# tes1.net
KiCad netlist of a schematic drawn in EAGLE
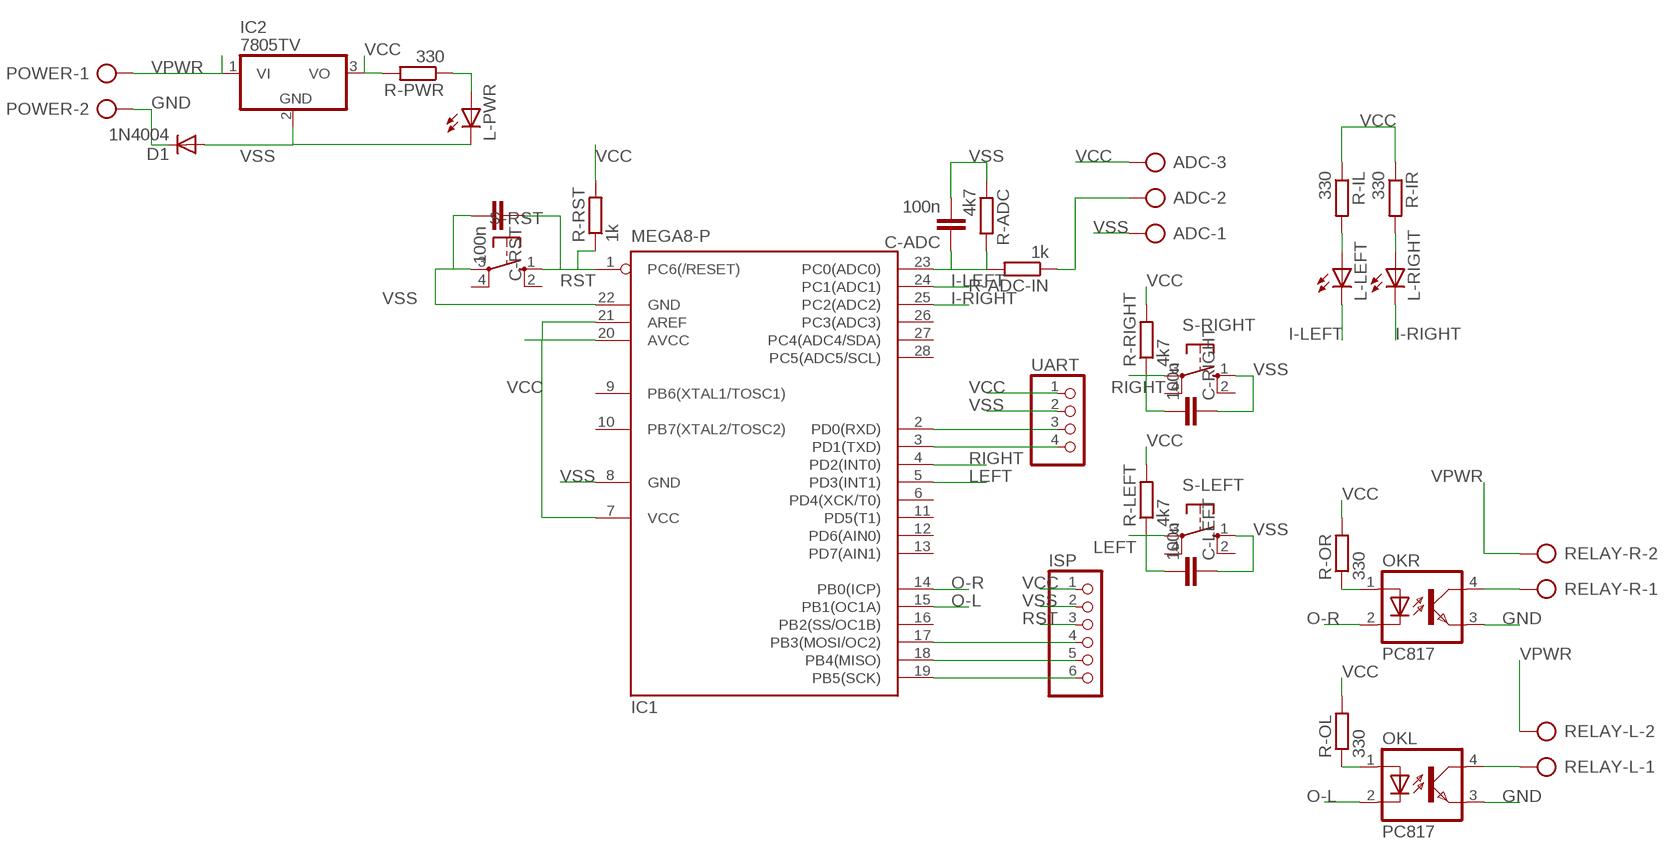
[diagram p0: schematic, sheet 1]

(export (version "E")
  (design (tool "Eeschema 10.0.6"))
  (components
    (comp (ref "ADC")
      (value "AK300/3")
      (footprint "eagle-import:AK300_3")
      (libsource (lib "eagle-import") (part "AK300/3"))
    )
    (comp (ref "C-ADC")
      (value "100n")
      (footprint "eagle-import:C050-024X044")
      (libsource (lib "eagle-import") (part "C-EU050-024X044"))
    )
    (comp (ref "C-LEFT")
      (value "100n")
      (footprint "eagle-import:C050-024X044")
      (libsource (lib "eagle-import") (part "C-EU050-024X044"))
    )
    (comp (ref "C-RIGHT")
      (value "100n")
      (footprint "eagle-import:C050-024X044")
      (libsource (lib "eagle-import") (part "C-EU050-024X044"))
    )
    (comp (ref "C-RST")
      (value "100n")
      (footprint "eagle-import:C050-024X044")
      (libsource (lib "eagle-import") (part "C-EU050-024X044"))
    )
    (comp (ref "D1")
      (value "1N4004")
      (footprint "eagle-import:DO41-10")
      (libsource (lib "eagle-import") (part "1N4004"))
    )
    (comp (ref "IC1")
      (value "MEGA8-P")
      (footprint "eagle-import:DIL28-3")
      (libsource (lib "eagle-import") (part "MEGA8-P"))
    )
    (comp (ref "IC2")
      (value "7805TV")
      (footprint "eagle-import:TO220V")
      (libsource (lib "eagle-import") (part "78TV05"))
    )
    (comp (ref "ISP")
      (value "PINHD-1X6")
      (footprint "eagle-import:1X06")
      (libsource (lib "eagle-import") (part "PINHD-1X6"))
    )
    (comp (ref "L-LEFT")
      (value "LED3MM")
      (footprint "eagle-import:LED3MM")
      (libsource (lib "eagle-import") (part "LED3MM"))
    )
    (comp (ref "L-PWR")
      (value "LED3MM")
      (footprint "eagle-import:LED3MM")
      (libsource (lib "eagle-import") (part "LED3MM"))
    )
    (comp (ref "L-RIGHT")
      (value "LED3MM")
      (footprint "eagle-import:LED3MM")
      (libsource (lib "eagle-import") (part "LED3MM"))
    )
    (comp (ref "OKL")
      (value "PC817")
      (footprint "eagle-import:DIL04")
      (fields (field (name "MPN") "PC817X4J000F"))
      (libsource (lib "eagle-import") (part "PC817"))
    )
    (comp (ref "OKR")
      (value "PC817")
      (footprint "eagle-import:DIL04")
      (fields (field (name "MPN") "PC817X4J000F"))
      (libsource (lib "eagle-import") (part "PC817"))
    )
    (comp (ref "POWER")
      (value "AK300/2")
      (footprint "eagle-import:AK300_2")
      (libsource (lib "eagle-import") (part "AK300/2"))
    )
    (comp (ref "R-ADC")
      (value "4k7")
      (footprint "eagle-import:0204_7")
      (libsource (lib "eagle-import") (part "R-EU_0204/7"))
    )
    (comp (ref "R-ADC-IN")
      (value "1k")
      (footprint "eagle-import:0204_7")
      (libsource (lib "eagle-import") (part "R-EU_0204/7"))
    )
    (comp (ref "R-IL")
      (value "330")
      (footprint "eagle-import:0204_7")
      (libsource (lib "eagle-import") (part "R-EU_0204/7"))
    )
    (comp (ref "R-IR")
      (value "330")
      (footprint "eagle-import:0204_7")
      (libsource (lib "eagle-import") (part "R-EU_0204/7"))
    )
    (comp (ref "R-LEFT")
      (value "4k7")
      (footprint "eagle-import:0204_7")
      (libsource (lib "eagle-import") (part "R-EU_0204/7"))
    )
    (comp (ref "R-OL")
      (value "330")
      (footprint "eagle-import:0204_7")
      (libsource (lib "eagle-import") (part "R-EU_0204/7"))
    )
    (comp (ref "R-OR")
      (value "330")
      (footprint "eagle-import:0204_7")
      (libsource (lib "eagle-import") (part "R-EU_0204/7"))
    )
    (comp (ref "R-PWR")
      (value "330")
      (footprint "eagle-import:0204_7")
      (libsource (lib "eagle-import") (part "R-EU_0204/7"))
    )
    (comp (ref "R-RIGHT")
      (value "4k7")
      (footprint "eagle-import:0204_7")
      (libsource (lib "eagle-import") (part "R-EU_0204/7"))
    )
    (comp (ref "R-RST")
      (value "1k")
      (footprint "eagle-import:0204_7")
      (libsource (lib "eagle-import") (part "R-EU_0204/7"))
    )
    (comp (ref "RELAY-L")
      (value "AK300/2")
      (footprint "eagle-import:AK300_2")
      (libsource (lib "eagle-import") (part "AK300/2"))
    )
    (comp (ref "RELAY-R")
      (value "AK300/2")
      (footprint "eagle-import:AK300_2")
      (libsource (lib "eagle-import") (part "AK300/2"))
    )
    (comp (ref "S-LEFT")
      (value "10-XX")
      (footprint "eagle-import:B3F-10XX")
      (fields (field (name "MPN") "B3F-1000"))
      (libsource (lib "eagle-import") (part "10-XX"))
    )
    (comp (ref "S-RIGHT")
      (value "10-XX")
      (footprint "eagle-import:B3F-10XX")
      (fields (field (name "MPN") "B3F-1000"))
      (libsource (lib "eagle-import") (part "10-XX"))
    )
    (comp (ref "S-RST")
      (value "10-XX")
      (footprint "eagle-import:B3F-10XX")
      (fields (field (name "MPN") "B3F-1000"))
      (libsource (lib "eagle-import") (part "10-XX"))
    )
    (comp (ref "UART")
      (value "PINHD-1X4")
      (footprint "eagle-import:1X04")
      (libsource (lib "eagle-import") (part "PINHD-1X4"))
    )
  )
  (nets
    (net (code "1") (name "/GND") (class "Default")
      (node (ref "D1") (pin "C") (pinfunction "C_C") (pintype "passive"))
      (node (ref "OKL") (pin "3") (pinfunction "EMIT_3") (pintype "passive"))
      (node (ref "OKR") (pin "3") (pinfunction "EMIT_3") (pintype "passive"))
      (node (ref "POWER") (pin "2") (pinfunction "KL_2") (pintype "passive"))
    )
    (net (code "2") (name "/I-LEFT") (class "Default")
      (node (ref "IC1") (pin "24") (pinfunction "PC1(ADC1)_24") (pintype "bidirectional"))
      (node (ref "L-LEFT") (pin "K") (pinfunction "C_K") (pintype "passive"))
    )
    (net (code "3") (name "/I-RIGHT") (class "Default")
      (node (ref "IC1") (pin "25") (pinfunction "PC2(ADC2)_25") (pintype "bidirectional"))
      (node (ref "L-RIGHT") (pin "K") (pinfunction "C_K") (pintype "passive"))
    )
    (net (code "4") (name "/LEFT") (class "Default")
      (node (ref "C-LEFT") (pin "2") (pinfunction "2_2") (pintype "passive"))
      (node (ref "IC1") (pin "5") (pinfunction "PD3(INT1)_5") (pintype "bidirectional"))
      (node (ref "R-LEFT") (pin "1") (pinfunction "1_1") (pintype "passive"))
      (node (ref "S-LEFT") (pin "3") (pinfunction "P_3") (pintype "passive"))
    )
    (net (code "5") (name "/O-L") (class "Default")
      (node (ref "IC1") (pin "15") (pinfunction "PB1(OC1A)_15") (pintype "bidirectional"))
      (node (ref "OKL") (pin "2") (pinfunction "C_2") (pintype "passive"))
    )
    (net (code "6") (name "/O-R") (class "Default")
      (node (ref "IC1") (pin "14") (pinfunction "PB0(ICP)_14") (pintype "bidirectional"))
      (node (ref "OKR") (pin "2") (pinfunction "C_2") (pintype "passive"))
    )
    (net (code "7") (name "/RIGHT") (class "Default")
      (node (ref "C-RIGHT") (pin "2") (pinfunction "2_2") (pintype "passive"))
      (node (ref "IC1") (pin "4") (pinfunction "PD2(INT0)_4") (pintype "bidirectional"))
      (node (ref "R-RIGHT") (pin "1") (pinfunction "1_1") (pintype "passive"))
      (node (ref "S-RIGHT") (pin "3") (pinfunction "P_3") (pintype "passive"))
    )
    (net (code "8") (name "/RST") (class "Default")
      (node (ref "C-RST") (pin "1") (pinfunction "1_1") (pintype "passive"))
      (node (ref "IC1") (pin "1") (pinfunction "PC6(/RESET)_1") (pintype "bidirectional"))
      (node (ref "ISP") (pin "3") (pinfunction "3_3") (pintype "passive"))
      (node (ref "R-RST") (pin "1") (pinfunction "1_1") (pintype "passive"))
      (node (ref "S-RST") (pin "1") (pinfunction "S_1") (pintype "passive"))
    )
    (net (code "9") (name "/VCC") (class "Default")
      (node (ref "ADC") (pin "3") (pinfunction "KL_3") (pintype "passive"))
      (node (ref "IC1") (pin "20") (pinfunction "AVCC_20") (pintype "power_in"))
      (node (ref "IC1") (pin "21") (pinfunction "AREF_21") (pintype "passive"))
      (node (ref "IC1") (pin "7") (pinfunction "VCC_7") (pintype "power_in"))
      (node (ref "IC2") (pin "3") (pinfunction "VO_3") (pintype "passive"))
      (node (ref "ISP") (pin "1") (pinfunction "1_1") (pintype "passive"))
      (node (ref "R-IL") (pin "1") (pinfunction "1_1") (pintype "passive"))
      (node (ref "R-IR") (pin "1") (pinfunction "1_1") (pintype "passive"))
      (node (ref "R-LEFT") (pin "2") (pinfunction "2_2") (pintype "passive"))
      (node (ref "R-OL") (pin "2") (pinfunction "2_2") (pintype "passive"))
      (node (ref "R-OR") (pin "2") (pinfunction "2_2") (pintype "passive"))
      (node (ref "R-PWR") (pin "2") (pinfunction "2_2") (pintype "passive"))
      (node (ref "R-RIGHT") (pin "2") (pinfunction "2_2") (pintype "passive"))
      (node (ref "R-RST") (pin "2") (pinfunction "2_2") (pintype "passive"))
      (node (ref "UART") (pin "1") (pinfunction "1_1") (pintype "passive"))
    )
    (net (code "10") (name "/VPWR") (class "Default")
      (node (ref "IC2") (pin "1") (pinfunction "VI_1") (pintype "input"))
      (node (ref "POWER") (pin "1") (pinfunction "KL_1") (pintype "passive"))
      (node (ref "RELAY-L") (pin "2") (pinfunction "KL_2") (pintype "passive"))
      (node (ref "RELAY-R") (pin "2") (pinfunction "KL_2") (pintype "passive"))
    )
    (net (code "11") (name "/VSS") (class "Default")
      (node (ref "ADC") (pin "1") (pinfunction "KL_1") (pintype "passive"))
      (node (ref "C-ADC") (pin "2") (pinfunction "2_2") (pintype "passive"))
      (node (ref "C-LEFT") (pin "1") (pinfunction "1_1") (pintype "passive"))
      (node (ref "C-RIGHT") (pin "1") (pinfunction "1_1") (pintype "passive"))
      (node (ref "C-RST") (pin "2") (pinfunction "2_2") (pintype "passive"))
      (node (ref "D1") (pin "A") (pinfunction "A_A") (pintype "passive"))
      (node (ref "IC1") (pin "22") (pinfunction "GND_22") (pintype "power_in"))
      (node (ref "IC1") (pin "8") (pinfunction "GND_8") (pintype "power_in"))
      (node (ref "IC2") (pin "2") (pinfunction "GND_2") (pintype "passive"))
      (node (ref "ISP") (pin "2") (pinfunction "2_2") (pintype "passive"))
      (node (ref "L-PWR") (pin "K") (pinfunction "C_K") (pintype "passive"))
      (node (ref "R-ADC") (pin "1") (pinfunction "1_1") (pintype "passive"))
      (node (ref "S-LEFT") (pin "1") (pinfunction "S_1") (pintype "passive"))
      (node (ref "S-RIGHT") (pin "1") (pinfunction "S_1") (pintype "passive"))
      (node (ref "S-RST") (pin "3") (pinfunction "P_3") (pintype "passive"))
      (node (ref "UART") (pin "2") (pinfunction "2_2") (pintype "passive"))
    )
    (net (code "12") (name "Net-(ADCB-KL)") (class "Default")
      (node (ref "ADC") (pin "2") (pinfunction "KL_2") (pintype "passive"))
      (node (ref "R-ADC-IN") (pin "1") (pinfunction "1_1") (pintype "passive"))
    )
    (net (code "13") (name "Net-(IC1-PB3(MOSI{slash}OC2))") (class "Default")
      (node (ref "IC1") (pin "17") (pinfunction "PB3(MOSI/OC2)_17") (pintype "bidirectional"))
      (node (ref "ISP") (pin "4") (pinfunction "4_4") (pintype "passive"))
    )
    (net (code "14") (name "Net-(IC1-PB4(MISO))") (class "Default")
      (node (ref "IC1") (pin "18") (pinfunction "PB4(MISO)_18") (pintype "bidirectional"))
      (node (ref "ISP") (pin "5") (pinfunction "5_5") (pintype "passive"))
    )
    (net (code "15") (name "Net-(IC1-PB5(SCK))") (class "Default")
      (node (ref "IC1") (pin "19") (pinfunction "PB5(SCK)_19") (pintype "bidirectional"))
      (node (ref "ISP") (pin "6") (pinfunction "6_6") (pintype "passive"))
    )
    (net (code "16") (name "Net-(IC1-PC0(ADC0))") (class "Default")
      (node (ref "C-ADC") (pin "1") (pinfunction "1_1") (pintype "passive"))
      (node (ref "IC1") (pin "23") (pinfunction "PC0(ADC0)_23") (pintype "bidirectional"))
      (node (ref "R-ADC") (pin "2") (pinfunction "2_2") (pintype "passive"))
      (node (ref "R-ADC-IN") (pin "2") (pinfunction "2_2") (pintype "passive"))
    )
    (net (code "17") (name "Net-(IC1-PD0(RXD))") (class "Default")
      (node (ref "IC1") (pin "2") (pinfunction "PD0(RXD)_2") (pintype "bidirectional"))
      (node (ref "UART") (pin "3") (pinfunction "3_3") (pintype "passive"))
    )
    (net (code "18") (name "Net-(IC1-PD1(TXD))") (class "Default")
      (node (ref "IC1") (pin "3") (pinfunction "PD1(TXD)_3") (pintype "bidirectional"))
      (node (ref "UART") (pin "4") (pinfunction "4_4") (pintype "passive"))
    )
    (net (code "19") (name "Net-(L-LEFT-PadA)") (class "Default")
      (node (ref "L-LEFT") (pin "A") (pinfunction "A_A") (pintype "passive"))
      (node (ref "R-IL") (pin "2") (pinfunction "2_2") (pintype "passive"))
    )
    (net (code "20") (name "Net-(L-PWR-PadA)") (class "Default")
      (node (ref "L-PWR") (pin "A") (pinfunction "A_A") (pintype "passive"))
      (node (ref "R-PWR") (pin "1") (pinfunction "1_1") (pintype "passive"))
    )
    (net (code "21") (name "Net-(L-RIGHT-PadA)") (class "Default")
      (node (ref "L-RIGHT") (pin "A") (pinfunction "A_A") (pintype "passive"))
      (node (ref "R-IR") (pin "2") (pinfunction "2_2") (pintype "passive"))
    )
    (net (code "22") (name "Net-(OKL-A)") (class "Default")
      (node (ref "OKL") (pin "1") (pinfunction "A_1") (pintype "passive"))
      (node (ref "R-OL") (pin "1") (pinfunction "1_1") (pintype "passive"))
    )
    (net (code "23") (name "Net-(OKL-COL)") (class "Default")
      (node (ref "OKL") (pin "4") (pinfunction "COL_4") (pintype "passive"))
      (node (ref "RELAY-L") (pin "1") (pinfunction "KL_1") (pintype "passive"))
    )
    (net (code "24") (name "Net-(OKR-A)") (class "Default")
      (node (ref "OKR") (pin "1") (pinfunction "A_1") (pintype "passive"))
      (node (ref "R-OR") (pin "1") (pinfunction "1_1") (pintype "passive"))
    )
    (net (code "25") (name "Net-(OKR-COL)") (class "Default")
      (node (ref "OKR") (pin "4") (pinfunction "COL_4") (pintype "passive"))
      (node (ref "RELAY-R") (pin "1") (pinfunction "KL_1") (pintype "passive"))
    )
    (net (code "26") (name "unconnected-(IC1-PB2(SS{slash}OC1B)-Pad16)") (class "Default")
      (node (ref "IC1") (pin "16") (pinfunction "PB2(SS/OC1B)_16") (pintype "bidirectional"))
    )
    (net (code "27") (name "unconnected-(IC1-PB6(XTAL1{slash}TOSC1)-Pad9)") (class "Default")
      (node (ref "IC1") (pin "9") (pinfunction "PB6(XTAL1/TOSC1)_9") (pintype "bidirectional"))
    )
    (net (code "28") (name "unconnected-(IC1-PB7(XTAL2{slash}TOSC2)-Pad10)") (class "Default")
      (node (ref "IC1") (pin "10") (pinfunction "PB7(XTAL2/TOSC2)_10") (pintype "bidirectional"))
    )
    (net (code "29") (name "unconnected-(IC1-PC3(ADC3)-Pad26)") (class "Default")
      (node (ref "IC1") (pin "26") (pinfunction "PC3(ADC3)_26") (pintype "bidirectional"))
    )
    (net (code "30") (name "unconnected-(IC1-PC4(ADC4{slash}SDA)-Pad27)") (class "Default")
      (node (ref "IC1") (pin "27") (pinfunction "PC4(ADC4/SDA)_27") (pintype "bidirectional"))
    )
    (net (code "31") (name "unconnected-(IC1-PC5(ADC5{slash}SCL)-Pad28)") (class "Default")
      (node (ref "IC1") (pin "28") (pinfunction "PC5(ADC5/SCL)_28") (pintype "bidirectional"))
    )
    (net (code "32") (name "unconnected-(IC1-PD4(XCK{slash}T0)-Pad6)") (class "Default")
      (node (ref "IC1") (pin "6") (pinfunction "PD4(XCK/T0)_6") (pintype "bidirectional"))
    )
    (net (code "33") (name "unconnected-(IC1-PD5(T1)-Pad11)") (class "Default")
      (node (ref "IC1") (pin "11") (pinfunction "PD5(T1)_11") (pintype "bidirectional"))
    )
    (net (code "34") (name "unconnected-(IC1-PD6(AIN0)-Pad12)") (class "Default")
      (node (ref "IC1") (pin "12") (pinfunction "PD6(AIN0)_12") (pintype "bidirectional"))
    )
    (net (code "35") (name "unconnected-(IC1-PD7(AIN1)-Pad13)") (class "Default")
      (node (ref "IC1") (pin "13") (pinfunction "PD7(AIN1)_13") (pintype "bidirectional"))
    )
    (net (code "36") (name "unconnected-(S-LEFT-P1-Pad4)") (class "Default")
      (node (ref "S-LEFT") (pin "4") (pinfunction "P1_4") (pintype "passive"))
    )
    (net (code "37") (name "unconnected-(S-LEFT-S1-Pad2)") (class "Default")
      (node (ref "S-LEFT") (pin "2") (pinfunction "S1_2") (pintype "passive"))
    )
    (net (code "38") (name "unconnected-(S-RIGHT-P1-Pad4)") (class "Default")
      (node (ref "S-RIGHT") (pin "4") (pinfunction "P1_4") (pintype "passive"))
    )
    (net (code "39") (name "unconnected-(S-RIGHT-S1-Pad2)") (class "Default")
      (node (ref "S-RIGHT") (pin "2") (pinfunction "S1_2") (pintype "passive"))
    )
    (net (code "40") (name "unconnected-(S-RST-P1-Pad4)") (class "Default")
      (node (ref "S-RST") (pin "4") (pinfunction "P1_4") (pintype "passive"))
    )
    (net (code "41") (name "unconnected-(S-RST-S1-Pad2)") (class "Default")
      (node (ref "S-RST") (pin "2") (pinfunction "S1_2") (pintype "passive"))
    )
  )
)
